# Master.net
KiCad netlist of a schematic drawn in Altium Designer
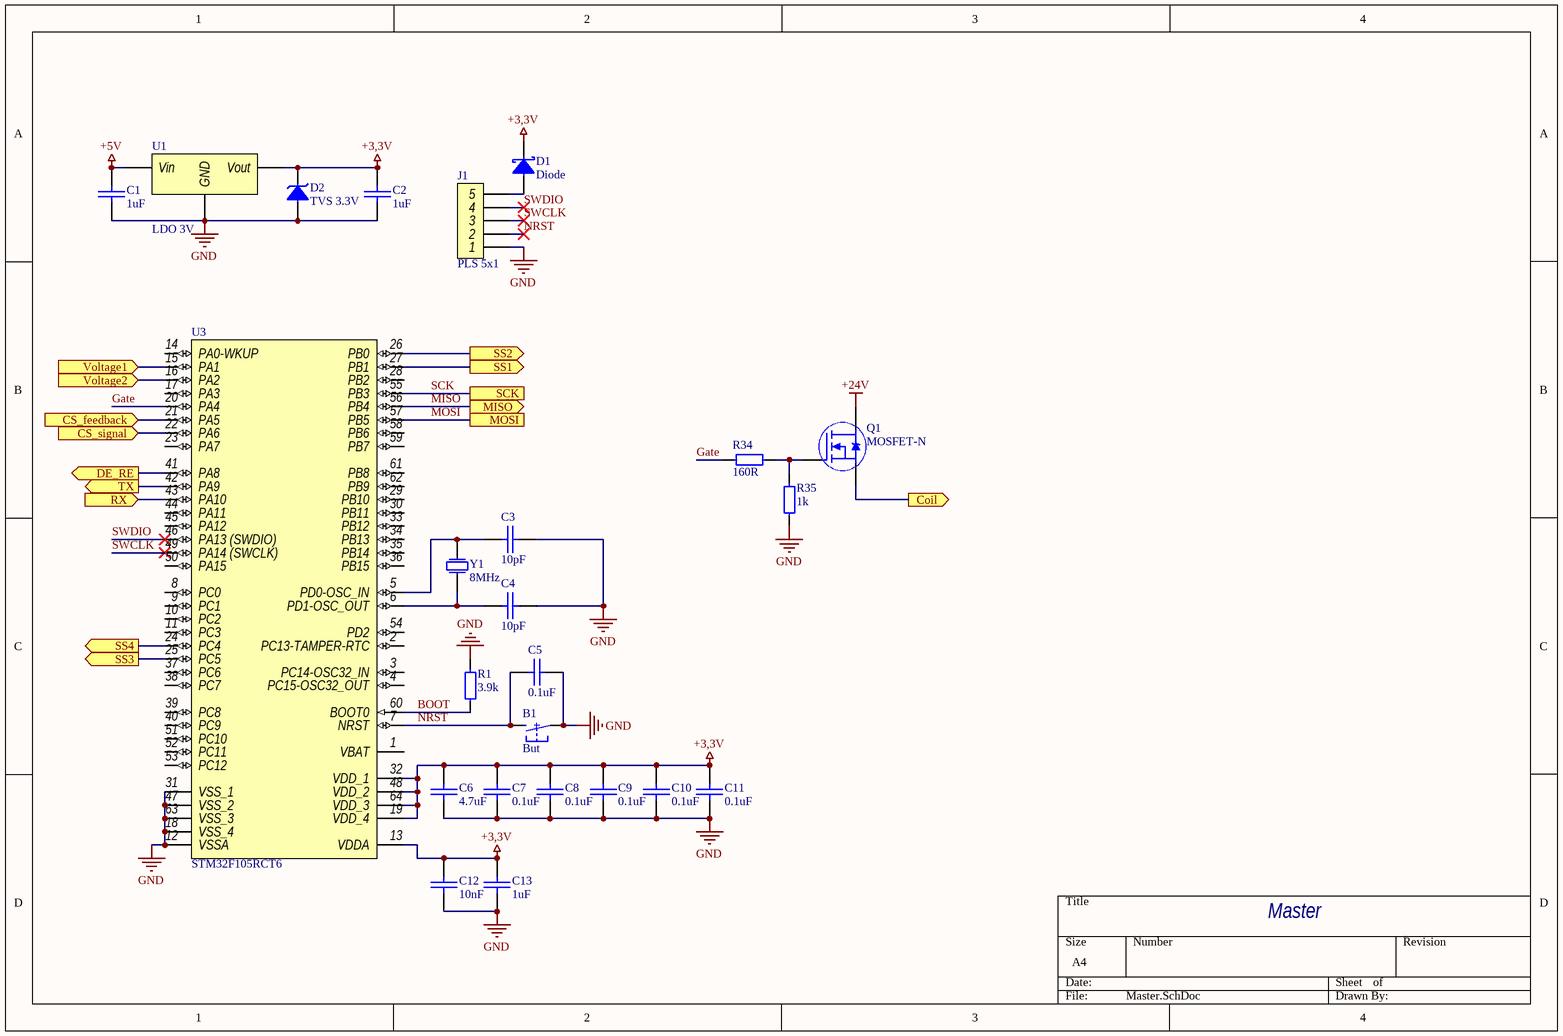
[diagram p0: Master.SchDoc]

(export (version "E")
  (design (tool "Eeschema 10.0.6"))
  (components
    (comp (ref "B1")
      (value "But")
      (footprint "BUTTON 6x3.5")
      (description "Button 2 Conn SMD")
      (fields
        (field (name "PART NUMBER") "L-KLS7-TS3608-5.0-180")
        (field (name "MANUFACTURER") "KLS electronic co ltd")
      )
      (libsource (lib "БУС") (part "Button 2 Conn"))
    )
    (comp (ref "C1")
      (value "1uF")
      (footprint "0603 Capicator")
      (description "1uF X5R 25V 10% 0603")
      (fields
        (field (name "MANUFACTURER") "Murata Manufacturing")
        (field (name "PART NUMBER") "GRM188R61E105KAADD")
      )
      (libsource (lib "БУС") (part "Cap 1uF (0603)"))
    )
    (comp (ref "C2")
      (value "1uF")
      (footprint "0603 Capicator")
      (description "1uF X5R 25V 10% 0603")
      (fields
        (field (name "MANUFACTURER") "Murata Manufacturing")
        (field (name "PART NUMBER") "GRM188R61E105KAADD")
      )
      (libsource (lib "БУС") (part "Cap 1uF (0603)"))
    )
    (comp (ref "C3")
      (value "10pF")
      (footprint "0603 Capicator")
      (description "10pF NP0 50V 5% 0603")
      (fields
        (field (name "MANUFACTURER") "Murata Manufacturing")
        (field (name "PART NUMBER") "GRM1885C1H100JA01D")
      )
      (libsource (lib "БУС") (part "Cap 10pF (0603)"))
    )
    (comp (ref "C4")
      (value "10pF")
      (footprint "0603 Capicator")
      (description "10pF NP0 50V 5% 0603")
      (fields
        (field (name "MANUFACTURER") "Murata Manufacturing")
        (field (name "PART NUMBER") "GRM1885C1H100JA01D")
      )
      (libsource (lib "БУС") (part "Cap 10pF (0603)"))
    )
    (comp (ref "C5")
      (value "0.1uF")
      (footprint "0603 Capicator")
      (description "0.1uF X7R 16V 10% 0603")
      (fields
        (field (name "MANUFACTURER") "Murata Manufacturing")
        (field (name "PART NUMBER") "GRM188R71C104KA01D")
      )
      (libsource (lib "БУС") (part "Cap 0.1uF (0603)"))
    )
    (comp (ref "C6")
      (value "4.7uF")
      (footprint "0603 Capicator")
      (description "4.7uF X5R 25V 10% 0603")
      (fields
        (field (name "MANUFACTURER") "Murata Manufacturing")
        (field (name "PART NUMBER") "GRM188R61E475KE11D")
      )
      (libsource (lib "БУС") (part "Cap 4.7uF (0603)"))
    )
    (comp (ref "C7")
      (value "0.1uF")
      (footprint "0603 Capicator")
      (description "0.1uF X7R 16V 10% 0603")
      (fields
        (field (name "MANUFACTURER") "Murata Manufacturing")
        (field (name "PART NUMBER") "GRM188R71C104KA01D")
      )
      (libsource (lib "БУС") (part "Cap 0.1uF (0603)"))
    )
    (comp (ref "C8")
      (value "0.1uF")
      (footprint "0603 Capicator")
      (description "0.1uF X7R 16V 10% 0603")
      (fields
        (field (name "MANUFACTURER") "Murata Manufacturing")
        (field (name "PART NUMBER") "GRM188R71C104KA01D")
      )
      (libsource (lib "БУС") (part "Cap 0.1uF (0603)"))
    )
    (comp (ref "C9")
      (value "0.1uF")
      (footprint "0603 Capicator")
      (description "0.1uF X7R 16V 10% 0603")
      (fields
        (field (name "MANUFACTURER") "Murata Manufacturing")
        (field (name "PART NUMBER") "GRM188R71C104KA01D")
      )
      (libsource (lib "БУС") (part "Cap 0.1uF (0603)"))
    )
    (comp (ref "C10")
      (value "0.1uF")
      (footprint "0603 Capicator")
      (description "0.1uF X7R 16V 10% 0603")
      (fields
        (field (name "MANUFACTURER") "Murata Manufacturing")
        (field (name "PART NUMBER") "GRM188R71C104KA01D")
      )
      (libsource (lib "БУС") (part "Cap 0.1uF (0603)"))
    )
    (comp (ref "C11")
      (value "0.1uF")
      (footprint "0603 Capicator")
      (description "0.1uF X7R 16V 10% 0603")
      (fields
        (field (name "MANUFACTURER") "Murata Manufacturing")
        (field (name "PART NUMBER") "GRM188R71C104KA01D")
      )
      (libsource (lib "БУС") (part "Cap 0.1uF (0603)"))
    )
    (comp (ref "C12")
      (value "10nF")
      (footprint "0603 Capicator")
      (description "10nF X7R  100V 10% 0603")
      (fields
        (field (name "MANUFACTURER") "Murata Manufacturing")
        (field (name "PART NUMBER") "GRM188R72A103KA01D")
      )
      (libsource (lib "БУС") (part "Cap 10nF (0603)"))
    )
    (comp (ref "C13")
      (value "1uF")
      (footprint "0603 Capicator")
      (description "1uF X5R 25V 10% 0603")
      (fields
        (field (name "MANUFACTURER") "Murata Manufacturing")
        (field (name "PART NUMBER") "GRM188R61E105KAADD")
      )
      (libsource (lib "БУС") (part "Cap 1uF (0603)"))
    )
    (comp (ref "D1")
      (value "Diode")
      (footprint "sod-123")
      (description "0.5 A, Low Forward Voltage less than 385 mV, 400 mW Power Dissipation Package")
      (fields (field (name "PART NUMBER") "MBR0520L") (field (name "MANUFACTURER") "ON Semiconductor"))
      (libsource (lib "БУС") (part "Diode Schottky (SOD-123)"))
    )
    (comp (ref "D2")
      (value "TVS 3.3V")
      (footprint "DO-216AA")
      (description "High peak pulse power: 200 W (10/1000 μs)")
      (fields (field (name "PART NUMBER") "SM2T3V3A") (field (name "MANUFACTURER") "STMicroelectronics"))
      (libsource (lib "БУС") (part "TVS Diode 3.3V [SM2T]"))
    )
    (comp (ref "J1")
      (value "PLS 5x1")
      (footprint "PLS 5x1")
      (description "Header, 5-Pin")
      (libsource (lib "БУС") (part "Conn 5 (PLS)"))
    )
    (comp (ref "Q1")
      (value "MOSFET-N")
      (footprint "SOT-23")
      (description "VDS 30V,  VGS Max ± 20V, RDS 27-40mΩ,")
      (fields
        (field (name "PART NUMBER") "IRLML0030TRPBF")
        (field (name "MANUFACTURER") "Infineon Technologies")
      )
      (libsource (lib "БУС") (part "MOSFET-N [IRLML]"))
    )
    (comp (ref "R1")
      (value "3.9k")
      (footprint "0603 Resistor")
      (description "0.1W 0603 3.9k, 1%")
      (fields (field (name "PART NUMBER") "RC0603FR-073K9L") (field (name "MANUFACTURER") "Taiwan"))
      (libsource (lib "БУС") (part "Res 3.9k (0603)"))
    )
    (comp (ref "R34")
      (value "160R")
      (footprint "0603 Resistor")
      (description "0.1W 0603 160R, 1%")
      (fields (field (name "PART NUMBER") "RC0603FR-07160RL") (field (name "MANUFACTURER") "Taiwan"))
      (libsource (lib "БУС") (part "Res 160R (0603)"))
    )
    (comp (ref "R35")
      (value "1k")
      (footprint "0603 Resistor")
      (description "0.1W 0603 1k, 1%")
      (fields (field (name "PART NUMBER") "RC0603FR-071KL") (field (name "MANUFACTURER") "Taiwan"))
      (libsource (lib "БУС") (part "Res 1k (0603)"))
    )
    (comp (ref "U1")
      (value "LDO 3V")
      (footprint "SOT-23")
      (description "MCP1702 Low Dropout Voltage Regulator. The input operating range is specifiedfrom 2.7V to 13.2V")
      (fields (field (name "PART NUMBER") "MCP1702T-3002E/CB") (field (name "MANUFACTURER") "Microchip"))
      (libsource (lib "БУС") (part "LDO 3,3V [MCP]"))
    )
    (comp (ref "U3")
      (value "STM32F105RCT6")
      (footprint "LQFP64")
      (description "MCU ARM 256KB FLASH MEM 64-LQFP")
      (fields (field (name "MANUFACTURER") "STMicroelectronics"))
      (libsource (lib "БУС") (part "STM32F105RCT6"))
    )
    (comp (ref "Y1")
      (value "8MHz")
      (footprint "NX5032GA")
      (description "Crystal NX5032GA")
      (fields
        (field (name "MANUFACTURER") "Nihon Dempa Kogio (NDK)")
        (field (name "PART NUMBER") "NX5032GA-8MHz")
      )
      (libsource (lib "БУС") (part "Crystal 8MHz"))
    )
  )
  (nets
    (net (code "1") (name "+3,3V") (class "Default")
      (node (ref "C10") (pin "2") (pinfunction "2_2") (pintype "passive"))
      (node (ref "C11") (pin "2") (pinfunction "2_2") (pintype "passive"))
      (node (ref "C12") (pin "2") (pinfunction "2_2") (pintype "passive"))
      (node (ref "C13") (pin "2") (pinfunction "2_2") (pintype "passive"))
      (node (ref "C2") (pin "2") (pinfunction "2_2") (pintype "passive"))
      (node (ref "C6") (pin "2") (pinfunction "2_2") (pintype "passive"))
      (node (ref "C7") (pin "2") (pinfunction "2_2") (pintype "passive"))
      (node (ref "C8") (pin "2") (pinfunction "2_2") (pintype "passive"))
      (node (ref "C9") (pin "2") (pinfunction "2_2") (pintype "passive"))
      (node (ref "D1") (pin "2") (pinfunction "2_2") (pintype "passive"))
      (node (ref "D2") (pin "2") (pinfunction "2_2") (pintype "passive"))
      (node (ref "U1") (pin "2") (pinfunction "Vout_2") (pintype "power_in"))
      (node (ref "U3") (pin "13") (pinfunction "VDDA_13") (pintype "power_in"))
      (node (ref "U3") (pin "19") (pinfunction "VDD_4_19") (pintype "power_in"))
      (node (ref "U3") (pin "32") (pinfunction "VDD_1_32") (pintype "power_in"))
      (node (ref "U3") (pin "48") (pinfunction "VDD_2_48") (pintype "power_in"))
      (node (ref "U3") (pin "64") (pinfunction "VDD_3_64") (pintype "power_in"))
    )
    (net (code "2") (name "+5V") (class "Default")
      (node (ref "C1") (pin "2") (pinfunction "2_2") (pintype "passive"))
      (node (ref "U1") (pin "3") (pinfunction "Vin_3") (pintype "power_in"))
    )
    (net (code "3") (name "+24V") (class "Default")
      (node (ref "Q1") (pin "3") (pinfunction "Drain_3") (pintype "passive"))
    )
    (net (code "4") (name "/BOOT") (class "Default")
      (node (ref "R1") (pin "1") (pinfunction "1_1") (pintype "passive"))
      (node (ref "U3") (pin "60") (pinfunction "BOOT0_60") (pintype "input"))
    )
    (net (code "5") (name "/CS_feedback") (class "Default")
      (node (ref "U3") (pin "21") (pinfunction "PA5_21") (pintype "bidirectional"))
    )
    (net (code "6") (name "/CS_signal") (class "Default")
      (node (ref "U3") (pin "22") (pinfunction "PA6_22") (pintype "bidirectional"))
    )
    (net (code "7") (name "/Coil") (class "Default")
      (node (ref "Q1") (pin "2") (pinfunction "Source_2") (pintype "passive"))
    )
    (net (code "8") (name "/DE_RE") (class "Default")
      (node (ref "U3") (pin "41") (pinfunction "PA8_41") (pintype "bidirectional"))
    )
    (net (code "9") (name "/Gate") (class "Default")
      (node (ref "R34") (pin "1") (pinfunction "1_1") (pintype "passive"))
      (node (ref "U3") (pin "20") (pinfunction "PA4_20") (pintype "bidirectional"))
    )
    (net (code "10") (name "/MISO") (class "Default")
      (node (ref "U3") (pin "56") (pinfunction "PB4_56") (pintype "bidirectional"))
    )
    (net (code "11") (name "/MOSI") (class "Default")
      (node (ref "U3") (pin "57") (pinfunction "PB5_57") (pintype "bidirectional"))
    )
    (net (code "12") (name "/NRST") (class "Default")
      (node (ref "B1") (pin "2") (pinfunction "2_2") (pintype "passive"))
      (node (ref "C5") (pin "1") (pinfunction "1_1") (pintype "passive"))
      (node (ref "J1") (pin "2") (pinfunction "2_2") (pintype "passive"))
      (node (ref "U3") (pin "7") (pinfunction "NRST_7") (pintype "bidirectional"))
    )
    (net (code "13") (name "/RX") (class "Default")
      (node (ref "U3") (pin "43") (pinfunction "PA10_43") (pintype "bidirectional"))
    )
    (net (code "14") (name "/SCK") (class "Default")
      (node (ref "U3") (pin "55") (pinfunction "PB3_55") (pintype "bidirectional"))
    )
    (net (code "15") (name "/SS1") (class "Default")
      (node (ref "U3") (pin "27") (pinfunction "PB1_27") (pintype "bidirectional"))
    )
    (net (code "16") (name "/SS2") (class "Default")
      (node (ref "U3") (pin "26") (pinfunction "PB0_26") (pintype "bidirectional"))
    )
    (net (code "17") (name "/SS3") (class "Default")
      (node (ref "U3") (pin "25") (pinfunction "PC5_25") (pintype "bidirectional"))
    )
    (net (code "18") (name "/SS4") (class "Default")
      (node (ref "U3") (pin "24") (pinfunction "PC4_24") (pintype "bidirectional"))
    )
    (net (code "19") (name "/SWCLK") (class "Default")
      (node (ref "J1") (pin "3") (pinfunction "3_3") (pintype "passive"))
      (node (ref "U3") (pin "49") (pinfunction "PA14_(SWCLK)_49") (pintype "bidirectional"))
    )
    (net (code "20") (name "/SWDIO") (class "Default")
      (node (ref "J1") (pin "4") (pinfunction "4_4") (pintype "passive"))
      (node (ref "U3") (pin "46") (pinfunction "PA13_(SWDIO)_46") (pintype "bidirectional"))
    )
    (net (code "21") (name "/TX") (class "Default")
      (node (ref "U3") (pin "42") (pinfunction "PA9_42") (pintype "bidirectional"))
    )
    (net (code "22") (name "/Voltage1") (class "Default")
      (node (ref "U3") (pin "15") (pinfunction "PA1_15") (pintype "bidirectional"))
    )
    (net (code "23") (name "/Voltage2") (class "Default")
      (node (ref "U3") (pin "16") (pinfunction "PA2_16") (pintype "bidirectional"))
    )
    (net (code "24") (name "GND") (class "Default")
      (node (ref "B1") (pin "1") (pinfunction "1_1") (pintype "passive"))
      (node (ref "C1") (pin "1") (pinfunction "1_1") (pintype "passive"))
      (node (ref "C10") (pin "1") (pinfunction "1_1") (pintype "passive"))
      (node (ref "C11") (pin "1") (pinfunction "1_1") (pintype "passive"))
      (node (ref "C12") (pin "1") (pinfunction "1_1") (pintype "passive"))
      (node (ref "C13") (pin "1") (pinfunction "1_1") (pintype "passive"))
      (node (ref "C2") (pin "1") (pinfunction "1_1") (pintype "passive"))
      (node (ref "C3") (pin "2") (pinfunction "2_2") (pintype "passive"))
      (node (ref "C4") (pin "2") (pinfunction "2_2") (pintype "passive"))
      (node (ref "C5") (pin "2") (pinfunction "2_2") (pintype "passive"))
      (node (ref "C6") (pin "1") (pinfunction "1_1") (pintype "passive"))
      (node (ref "C7") (pin "1") (pinfunction "1_1") (pintype "passive"))
      (node (ref "C8") (pin "1") (pinfunction "1_1") (pintype "passive"))
      (node (ref "C9") (pin "1") (pinfunction "1_1") (pintype "passive"))
      (node (ref "D2") (pin "1") (pinfunction "1_1") (pintype "passive"))
      (node (ref "J1") (pin "1") (pinfunction "1_1") (pintype "passive"))
      (node (ref "R1") (pin "2") (pinfunction "2_2") (pintype "passive"))
      (node (ref "R35") (pin "1") (pinfunction "1_1") (pintype "passive"))
      (node (ref "U1") (pin "1") (pinfunction "GND_1") (pintype "power_in"))
      (node (ref "U3") (pin "12") (pinfunction "VSSA_12") (pintype "power_in"))
      (node (ref "U3") (pin "18") (pinfunction "VSS_4_18") (pintype "power_in"))
      (node (ref "U3") (pin "31") (pinfunction "VSS_1_31") (pintype "power_in"))
      (node (ref "U3") (pin "47") (pinfunction "VSS_2_47") (pintype "power_in"))
      (node (ref "U3") (pin "63") (pinfunction "VSS_3_63") (pintype "power_in"))
    )
    (net (code "25") (name "Net-(D1-Pad1)") (class "Default")
      (node (ref "D1") (pin "1") (pinfunction "1_1") (pintype "passive"))
      (node (ref "J1") (pin "5") (pinfunction "5_5") (pintype "passive"))
    )
    (net (code "26") (name "Net-(Q1-Gate)") (class "Default")
      (node (ref "Q1") (pin "1") (pinfunction "Gate_1") (pintype "passive"))
      (node (ref "R34") (pin "2") (pinfunction "2_2") (pintype "passive"))
      (node (ref "R35") (pin "2") (pinfunction "2_2") (pintype "passive"))
    )
    (net (code "27") (name "Net-(U3-PD0-OSC_IN)") (class "Default")
      (node (ref "C3") (pin "1") (pinfunction "1_1") (pintype "passive"))
      (node (ref "U3") (pin "5") (pinfunction "PD0-OSC_IN_5") (pintype "bidirectional"))
      (node (ref "Y1") (pin "2") (pinfunction "2_2") (pintype "passive"))
    )
    (net (code "28") (name "Net-(U3-PD1-OSC_OUT)") (class "Default")
      (node (ref "C4") (pin "1") (pinfunction "1_1") (pintype "passive"))
      (node (ref "U3") (pin "6") (pinfunction "PD1-OSC_OUT_6") (pintype "bidirectional"))
      (node (ref "Y1") (pin "1") (pinfunction "1_1") (pintype "passive"))
    )
    (net (code "29") (name "unconnected-(U3-PA0-WKUP-Pad14)") (class "Default")
      (node (ref "U3") (pin "14") (pinfunction "PA0-WKUP_14") (pintype "bidirectional"))
    )
    (net (code "30") (name "unconnected-(U3-PA3-Pad17)") (class "Default")
      (node (ref "U3") (pin "17") (pinfunction "PA3_17") (pintype "bidirectional"))
    )
    (net (code "31") (name "unconnected-(U3-PA7-Pad23)") (class "Default")
      (node (ref "U3") (pin "23") (pinfunction "PA7_23") (pintype "bidirectional"))
    )
    (net (code "32") (name "unconnected-(U3-PA11-Pad44)") (class "Default")
      (node (ref "U3") (pin "44") (pinfunction "PA11_44") (pintype "bidirectional"))
    )
    (net (code "33") (name "unconnected-(U3-PA12-Pad45)") (class "Default")
      (node (ref "U3") (pin "45") (pinfunction "PA12_45") (pintype "bidirectional"))
    )
    (net (code "34") (name "unconnected-(U3-PA15-Pad50)") (class "Default")
      (node (ref "U3") (pin "50") (pinfunction "PA15_50") (pintype "bidirectional"))
    )
    (net (code "35") (name "unconnected-(U3-PB2-Pad28)") (class "Default")
      (node (ref "U3") (pin "28") (pinfunction "PB2_28") (pintype "bidirectional"))
    )
    (net (code "36") (name "unconnected-(U3-PB6-Pad58)") (class "Default")
      (node (ref "U3") (pin "58") (pinfunction "PB6_58") (pintype "bidirectional"))
    )
    (net (code "37") (name "unconnected-(U3-PB7-Pad59)") (class "Default")
      (node (ref "U3") (pin "59") (pinfunction "PB7_59") (pintype "bidirectional"))
    )
    (net (code "38") (name "unconnected-(U3-PB8-Pad61)") (class "Default")
      (node (ref "U3") (pin "61") (pinfunction "PB8_61") (pintype "bidirectional"))
    )
    (net (code "39") (name "unconnected-(U3-PB9-Pad62)") (class "Default")
      (node (ref "U3") (pin "62") (pinfunction "PB9_62") (pintype "bidirectional"))
    )
    (net (code "40") (name "unconnected-(U3-PB10-Pad29)") (class "Default")
      (node (ref "U3") (pin "29") (pinfunction "PB10_29") (pintype "bidirectional"))
    )
    (net (code "41") (name "unconnected-(U3-PB11-Pad30)") (class "Default")
      (node (ref "U3") (pin "30") (pinfunction "PB11_30") (pintype "bidirectional"))
    )
    (net (code "42") (name "unconnected-(U3-PB12-Pad33)") (class "Default")
      (node (ref "U3") (pin "33") (pinfunction "PB12_33") (pintype "bidirectional"))
    )
    (net (code "43") (name "unconnected-(U3-PB13-Pad34)") (class "Default")
      (node (ref "U3") (pin "34") (pinfunction "PB13_34") (pintype "bidirectional"))
    )
    (net (code "44") (name "unconnected-(U3-PB14-Pad35)") (class "Default")
      (node (ref "U3") (pin "35") (pinfunction "PB14_35") (pintype "bidirectional"))
    )
    (net (code "45") (name "unconnected-(U3-PB15-Pad36)") (class "Default")
      (node (ref "U3") (pin "36") (pinfunction "PB15_36") (pintype "bidirectional"))
    )
    (net (code "46") (name "unconnected-(U3-PC0-Pad8)") (class "Default")
      (node (ref "U3") (pin "8") (pinfunction "PC0_8") (pintype "bidirectional"))
    )
    (net (code "47") (name "unconnected-(U3-PC1-Pad9)") (class "Default")
      (node (ref "U3") (pin "9") (pinfunction "PC1_9") (pintype "bidirectional"))
    )
    (net (code "48") (name "unconnected-(U3-PC2-Pad10)") (class "Default")
      (node (ref "U3") (pin "10") (pinfunction "PC2_10") (pintype "bidirectional"))
    )
    (net (code "49") (name "unconnected-(U3-PC3-Pad11)") (class "Default")
      (node (ref "U3") (pin "11") (pinfunction "PC3_11") (pintype "bidirectional"))
    )
    (net (code "50") (name "unconnected-(U3-PC6-Pad37)") (class "Default")
      (node (ref "U3") (pin "37") (pinfunction "PC6_37") (pintype "bidirectional"))
    )
    (net (code "51") (name "unconnected-(U3-PC7-Pad38)") (class "Default")
      (node (ref "U3") (pin "38") (pinfunction "PC7_38") (pintype "bidirectional"))
    )
    (net (code "52") (name "unconnected-(U3-PC8-Pad39)") (class "Default")
      (node (ref "U3") (pin "39") (pinfunction "PC8_39") (pintype "bidirectional"))
    )
    (net (code "53") (name "unconnected-(U3-PC9-Pad40)") (class "Default")
      (node (ref "U3") (pin "40") (pinfunction "PC9_40") (pintype "bidirectional"))
    )
    (net (code "54") (name "unconnected-(U3-PC10-Pad51)") (class "Default")
      (node (ref "U3") (pin "51") (pinfunction "PC10_51") (pintype "bidirectional"))
    )
    (net (code "55") (name "unconnected-(U3-PC11-Pad52)") (class "Default")
      (node (ref "U3") (pin "52") (pinfunction "PC11_52") (pintype "bidirectional"))
    )
    (net (code "56") (name "unconnected-(U3-PC12-Pad53)") (class "Default")
      (node (ref "U3") (pin "53") (pinfunction "PC12_53") (pintype "bidirectional"))
    )
    (net (code "57") (name "unconnected-(U3-PC13-TAMPER-RTC-Pad2)") (class "Default")
      (node (ref "U3") (pin "2") (pinfunction "PC13-TAMPER-RTC_2") (pintype "bidirectional"))
    )
    (net (code "58") (name "unconnected-(U3-PC14-OSC32_IN-Pad3)") (class "Default")
      (node (ref "U3") (pin "3") (pinfunction "PC14-OSC32_IN_3") (pintype "bidirectional"))
    )
    (net (code "59") (name "unconnected-(U3-PC15-OSC32_OUT-Pad4)") (class "Default")
      (node (ref "U3") (pin "4") (pinfunction "PC15-OSC32_OUT_4") (pintype "bidirectional"))
    )
    (net (code "60") (name "unconnected-(U3-PD2-Pad54)") (class "Default")
      (node (ref "U3") (pin "54") (pinfunction "PD2_54") (pintype "bidirectional"))
    )
    (net (code "61") (name "unconnected-(U3-VBAT-Pad1)") (class "Default")
      (node (ref "U3") (pin "1") (pinfunction "VBAT_1") (pintype "power_in"))
    )
  )
)
